# 20-pin.net
KiCad netlist of a schematic drawn in EAGLE
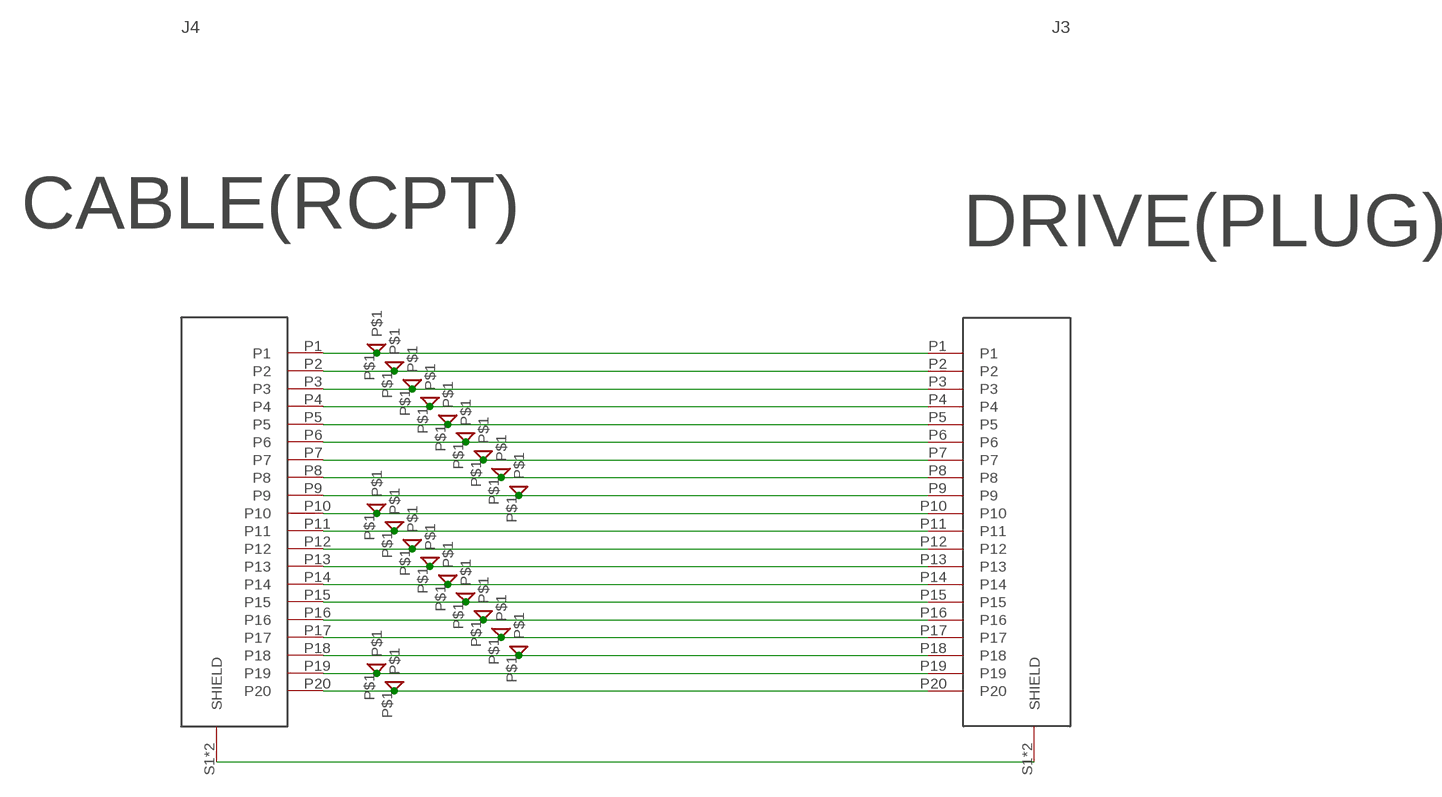
[diagram p0: schematic, sheet 1]

(export (version "E")
  (design (tool "Eeschema 10.0.6"))
  (components
    (comp (ref "J3")
      (value "3M_10120-52E2PC(PLUG)")
      (footprint "eagle-import:3M_10120-52E2PC(PLUG)")
      (libsource (lib "eagle-import") (part "3M_10120-52E2PC(PLUG)"))
    )
    (comp (ref "J4")
      (value "3M_10220-55H3PC(RECEPTACLE)")
      (footprint "eagle-import:3M_10220-55H3PC(RECEPTACLE)")
      (libsource (lib "eagle-import") (part "3M_10220-55H3PC(RECEPTACLE)"))
    )
    (comp (ref "U$1")
      (value "PTH_SMALL")
      (footprint "eagle-import:PTH_SMALL")
      (libsource (lib "eagle-import") (part "PTH_SMALL"))
    )
    (comp (ref "U$2")
      (value "PTH_SMALL")
      (footprint "eagle-import:PTH_SMALL")
      (libsource (lib "eagle-import") (part "PTH_SMALL"))
    )
    (comp (ref "U$3")
      (value "PTH_SMALL")
      (footprint "eagle-import:PTH_SMALL")
      (libsource (lib "eagle-import") (part "PTH_SMALL"))
    )
    (comp (ref "U$4")
      (value "PTH_SMALL")
      (footprint "eagle-import:PTH_SMALL")
      (libsource (lib "eagle-import") (part "PTH_SMALL"))
    )
    (comp (ref "U$5")
      (value "PTH_SMALL")
      (footprint "eagle-import:PTH_SMALL")
      (libsource (lib "eagle-import") (part "PTH_SMALL"))
    )
    (comp (ref "U$6")
      (value "PTH_SMALL")
      (footprint "eagle-import:PTH_SMALL")
      (libsource (lib "eagle-import") (part "PTH_SMALL"))
    )
    (comp (ref "U$7")
      (value "PTH_SMALL")
      (footprint "eagle-import:PTH_SMALL")
      (libsource (lib "eagle-import") (part "PTH_SMALL"))
    )
    (comp (ref "U$8")
      (value "PTH_SMALL")
      (footprint "eagle-import:PTH_SMALL")
      (libsource (lib "eagle-import") (part "PTH_SMALL"))
    )
    (comp (ref "U$9")
      (value "PTH_SMALL")
      (footprint "eagle-import:PTH_SMALL")
      (libsource (lib "eagle-import") (part "PTH_SMALL"))
    )
    (comp (ref "U$10")
      (value "PTH_SMALL")
      (footprint "eagle-import:PTH_SMALL")
      (libsource (lib "eagle-import") (part "PTH_SMALL"))
    )
    (comp (ref "U$11")
      (value "PTH_SMALL")
      (footprint "eagle-import:PTH_SMALL")
      (libsource (lib "eagle-import") (part "PTH_SMALL"))
    )
    (comp (ref "U$12")
      (value "PTH_SMALL")
      (footprint "eagle-import:PTH_SMALL")
      (libsource (lib "eagle-import") (part "PTH_SMALL"))
    )
    (comp (ref "U$13")
      (value "PTH_SMALL")
      (footprint "eagle-import:PTH_SMALL")
      (libsource (lib "eagle-import") (part "PTH_SMALL"))
    )
    (comp (ref "U$14")
      (value "PTH_SMALL")
      (footprint "eagle-import:PTH_SMALL")
      (libsource (lib "eagle-import") (part "PTH_SMALL"))
    )
    (comp (ref "U$15")
      (value "PTH_SMALL")
      (footprint "eagle-import:PTH_SMALL")
      (libsource (lib "eagle-import") (part "PTH_SMALL"))
    )
    (comp (ref "U$16")
      (value "PTH_SMALL")
      (footprint "eagle-import:PTH_SMALL")
      (libsource (lib "eagle-import") (part "PTH_SMALL"))
    )
    (comp (ref "U$17")
      (value "PTH_SMALL")
      (footprint "eagle-import:PTH_SMALL")
      (libsource (lib "eagle-import") (part "PTH_SMALL"))
    )
    (comp (ref "U$18")
      (value "PTH_SMALL")
      (footprint "eagle-import:PTH_SMALL")
      (libsource (lib "eagle-import") (part "PTH_SMALL"))
    )
    (comp (ref "U$19")
      (value "PTH_SMALL")
      (footprint "eagle-import:PTH_SMALL")
      (libsource (lib "eagle-import") (part "PTH_SMALL"))
    )
    (comp (ref "U$20")
      (value "PTH_SMALL")
      (footprint "eagle-import:PTH_SMALL")
      (libsource (lib "eagle-import") (part "PTH_SMALL"))
    )
  )
  (nets
    (net (code "1") (name "Net-(J3-PadP1)") (class "Default")
      (node (ref "J3") (pin "P1") (pinfunction "P1_P1") (pintype "bidirectional"))
      (node (ref "J4") (pin "P1") (pinfunction "P1_P1") (pintype "bidirectional"))
      (node (ref "U$1") (pin "P$1") (pinfunction "P$1_P$1") (pintype "bidirectional"))
    )
    (net (code "2") (name "Net-(J3-PadP2)") (class "Default")
      (node (ref "J3") (pin "P2") (pinfunction "P2_P2") (pintype "bidirectional"))
      (node (ref "J4") (pin "P2") (pinfunction "P2_P2") (pintype "bidirectional"))
      (node (ref "U$2") (pin "P$1") (pinfunction "P$1_P$1") (pintype "bidirectional"))
    )
    (net (code "3") (name "Net-(J3-PadP3)") (class "Default")
      (node (ref "J3") (pin "P3") (pinfunction "P3_P3") (pintype "bidirectional"))
      (node (ref "J4") (pin "P3") (pinfunction "P3_P3") (pintype "bidirectional"))
      (node (ref "U$3") (pin "P$1") (pinfunction "P$1_P$1") (pintype "bidirectional"))
    )
    (net (code "4") (name "Net-(J3-PadP4)") (class "Default")
      (node (ref "J3") (pin "P4") (pinfunction "P4_P4") (pintype "bidirectional"))
      (node (ref "J4") (pin "P4") (pinfunction "P4_P4") (pintype "bidirectional"))
      (node (ref "U$4") (pin "P$1") (pinfunction "P$1_P$1") (pintype "bidirectional"))
    )
    (net (code "5") (name "Net-(J3-PadP5)") (class "Default")
      (node (ref "J3") (pin "P5") (pinfunction "P5_P5") (pintype "bidirectional"))
      (node (ref "J4") (pin "P5") (pinfunction "P5_P5") (pintype "bidirectional"))
      (node (ref "U$5") (pin "P$1") (pinfunction "P$1_P$1") (pintype "bidirectional"))
    )
    (net (code "6") (name "Net-(J3-PadP6)") (class "Default")
      (node (ref "J3") (pin "P6") (pinfunction "P6_P6") (pintype "bidirectional"))
      (node (ref "J4") (pin "P6") (pinfunction "P6_P6") (pintype "bidirectional"))
      (node (ref "U$6") (pin "P$1") (pinfunction "P$1_P$1") (pintype "bidirectional"))
    )
    (net (code "7") (name "Net-(J3-PadP7)") (class "Default")
      (node (ref "J3") (pin "P7") (pinfunction "P7_P7") (pintype "bidirectional"))
      (node (ref "J4") (pin "P7") (pinfunction "P7_P7") (pintype "bidirectional"))
      (node (ref "U$7") (pin "P$1") (pinfunction "P$1_P$1") (pintype "bidirectional"))
    )
    (net (code "8") (name "Net-(J3-PadP8)") (class "Default")
      (node (ref "J3") (pin "P8") (pinfunction "P8_P8") (pintype "bidirectional"))
      (node (ref "J4") (pin "P8") (pinfunction "P8_P8") (pintype "bidirectional"))
      (node (ref "U$8") (pin "P$1") (pinfunction "P$1_P$1") (pintype "bidirectional"))
    )
    (net (code "9") (name "Net-(J3-PadP9)") (class "Default")
      (node (ref "J3") (pin "P9") (pinfunction "P9_P9") (pintype "bidirectional"))
      (node (ref "J4") (pin "P9") (pinfunction "P9_P9") (pintype "bidirectional"))
      (node (ref "U$9") (pin "P$1") (pinfunction "P$1_P$1") (pintype "bidirectional"))
    )
    (net (code "10") (name "Net-(J3-PadP10)") (class "Default")
      (node (ref "J3") (pin "P10") (pinfunction "P10_P10") (pintype "bidirectional"))
      (node (ref "J4") (pin "P10") (pinfunction "P10_P10") (pintype "bidirectional"))
      (node (ref "U$10") (pin "P$1") (pinfunction "P$1_P$1") (pintype "bidirectional"))
    )
    (net (code "11") (name "Net-(J3-PadP11)") (class "Default")
      (node (ref "J3") (pin "P11") (pinfunction "P11_P11") (pintype "bidirectional"))
      (node (ref "J4") (pin "P11") (pinfunction "P11_P11") (pintype "bidirectional"))
      (node (ref "U$11") (pin "P$1") (pinfunction "P$1_P$1") (pintype "bidirectional"))
    )
    (net (code "12") (name "Net-(J3-PadP12)") (class "Default")
      (node (ref "J3") (pin "P12") (pinfunction "P12_P12") (pintype "bidirectional"))
      (node (ref "J4") (pin "P12") (pinfunction "P12_P12") (pintype "bidirectional"))
      (node (ref "U$12") (pin "P$1") (pinfunction "P$1_P$1") (pintype "bidirectional"))
    )
    (net (code "13") (name "Net-(J3-PadP13)") (class "Default")
      (node (ref "J3") (pin "P13") (pinfunction "P13_P13") (pintype "bidirectional"))
      (node (ref "J4") (pin "P13") (pinfunction "P13_P13") (pintype "bidirectional"))
      (node (ref "U$13") (pin "P$1") (pinfunction "P$1_P$1") (pintype "bidirectional"))
    )
    (net (code "14") (name "Net-(J3-PadP14)") (class "Default")
      (node (ref "J3") (pin "P14") (pinfunction "P14_P14") (pintype "bidirectional"))
      (node (ref "J4") (pin "P14") (pinfunction "P14_P14") (pintype "bidirectional"))
      (node (ref "U$14") (pin "P$1") (pinfunction "P$1_P$1") (pintype "bidirectional"))
    )
    (net (code "15") (name "Net-(J3-PadP15)") (class "Default")
      (node (ref "J3") (pin "P15") (pinfunction "P15_P15") (pintype "bidirectional"))
      (node (ref "J4") (pin "P15") (pinfunction "P15_P15") (pintype "bidirectional"))
      (node (ref "U$15") (pin "P$1") (pinfunction "P$1_P$1") (pintype "bidirectional"))
    )
    (net (code "16") (name "Net-(J3-PadP16)") (class "Default")
      (node (ref "J3") (pin "P16") (pinfunction "P16_P16") (pintype "bidirectional"))
      (node (ref "J4") (pin "P16") (pinfunction "P16_P16") (pintype "bidirectional"))
      (node (ref "U$16") (pin "P$1") (pinfunction "P$1_P$1") (pintype "bidirectional"))
    )
    (net (code "17") (name "Net-(J3-PadP17)") (class "Default")
      (node (ref "J3") (pin "P17") (pinfunction "P17_P17") (pintype "bidirectional"))
      (node (ref "J4") (pin "P17") (pinfunction "P17_P17") (pintype "bidirectional"))
      (node (ref "U$17") (pin "P$1") (pinfunction "P$1_P$1") (pintype "bidirectional"))
    )
    (net (code "18") (name "Net-(J3-PadP18)") (class "Default")
      (node (ref "J3") (pin "P18") (pinfunction "P18_P18") (pintype "bidirectional"))
      (node (ref "J4") (pin "P18") (pinfunction "P18_P18") (pintype "bidirectional"))
      (node (ref "U$18") (pin "P$1") (pinfunction "P$1_P$1") (pintype "bidirectional"))
    )
    (net (code "19") (name "Net-(J3-PadP19)") (class "Default")
      (node (ref "J3") (pin "P19") (pinfunction "P19_P19") (pintype "bidirectional"))
      (node (ref "J4") (pin "P19") (pinfunction "P19_P19") (pintype "bidirectional"))
      (node (ref "U$19") (pin "P$1") (pinfunction "P$1_P$1") (pintype "bidirectional"))
    )
    (net (code "20") (name "Net-(J3-PadP20)") (class "Default")
      (node (ref "J3") (pin "P20") (pinfunction "P20_P20") (pintype "bidirectional"))
      (node (ref "J4") (pin "P20") (pinfunction "P20_P20") (pintype "bidirectional"))
      (node (ref "U$20") (pin "P$1") (pinfunction "P$1_P$1") (pintype "bidirectional"))
    )
    (net (code "21") (name "Net-(J3-SHIELD-PadS1)") (class "Default")
      (node (ref "J3") (pin "S1") (pinfunction "SHIELD_S1") (pintype "bidirectional"))
      (node (ref "J3") (pin "S2") (pinfunction "SHIELD_S2") (pintype "bidirectional"))
      (node (ref "J4") (pin "S1") (pinfunction "SHIELD_S1") (pintype "bidirectional"))
      (node (ref "J4") (pin "S2") (pinfunction "SHIELD_S2") (pintype "bidirectional"))
    )
  )
)
